# R2D2_Main_Board.net
KiCad netlist of a schematic drawn in EAGLE
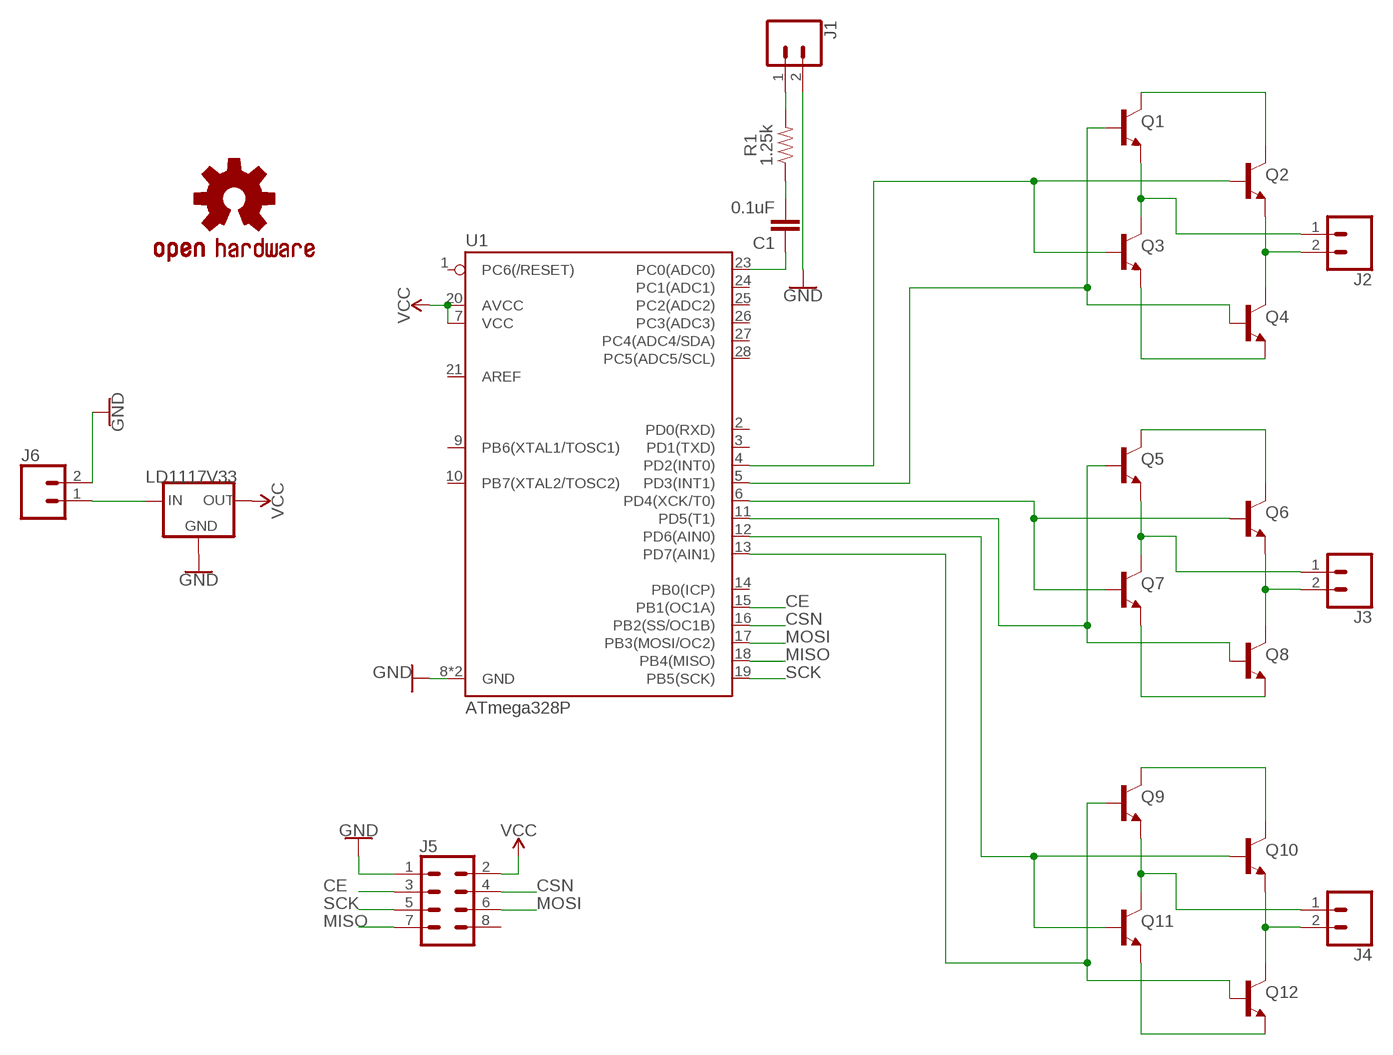
[diagram p0: schematic, sheet 1]

(export (version "E")
  (design (tool "Eeschema 10.0.6"))
  (components
    (comp (ref "C1")
      (value "0.1uF")
      (footprint "eagle-import:CAP-PTH-SMALL-KIT")
      (libsource (lib "eagle-import") (part "0.1UF-KIT-EZ-50V-20%"))
    )
    (comp (ref "J1")
      (value "CONN_02")
      (footprint "eagle-import:1X02")
      (libsource (lib "eagle-import") (part "CONN_02"))
    )
    (comp (ref "J2")
      (value "CONN_02")
      (footprint "eagle-import:1X02")
      (libsource (lib "eagle-import") (part "CONN_02"))
    )
    (comp (ref "J3")
      (value "CONN_02")
      (footprint "eagle-import:1X02")
      (libsource (lib "eagle-import") (part "CONN_02"))
    )
    (comp (ref "J4")
      (value "CONN_02")
      (footprint "eagle-import:1X02")
      (libsource (lib "eagle-import") (part "CONN_02"))
    )
    (comp (ref "J5")
      (value "CONN_04X2")
      (footprint "eagle-import:2X4")
      (libsource (lib "eagle-import") (part "CONN_04X2"))
    )
    (comp (ref "J6")
      (value "CONN_02")
      (footprint "eagle-import:1X02")
      (libsource (lib "eagle-import") (part "CONN_02"))
    )
    (comp (ref "LOGO1")
      (value "OSHW-LOGOL")
      (footprint "eagle-import:OSHW-LOGO-L")
      (libsource (lib "eagle-import") (part "OSHW-LOGOL"))
    )
    (comp (ref "Q1")
      (value "200mA/40V")
      (footprint "eagle-import:TO-92")
      (libsource (lib "eagle-import") (part "TRANS_NPN-2N3904"))
    )
    (comp (ref "Q2")
      (value "200mA/40V")
      (footprint "eagle-import:TO-92")
      (libsource (lib "eagle-import") (part "TRANS_NPN-2N3904"))
    )
    (comp (ref "Q3")
      (value "200mA/40V")
      (footprint "eagle-import:TO-92")
      (libsource (lib "eagle-import") (part "TRANS_NPN-2N3904"))
    )
    (comp (ref "Q4")
      (value "200mA/40V")
      (footprint "eagle-import:TO-92")
      (libsource (lib "eagle-import") (part "TRANS_NPN-2N3904"))
    )
    (comp (ref "Q5")
      (value "200mA/40V")
      (footprint "eagle-import:TO-92")
      (libsource (lib "eagle-import") (part "TRANS_NPN-2N3904"))
    )
    (comp (ref "Q6")
      (value "200mA/40V")
      (footprint "eagle-import:TO-92")
      (libsource (lib "eagle-import") (part "TRANS_NPN-2N3904"))
    )
    (comp (ref "Q7")
      (value "200mA/40V")
      (footprint "eagle-import:TO-92")
      (libsource (lib "eagle-import") (part "TRANS_NPN-2N3904"))
    )
    (comp (ref "Q8")
      (value "200mA/40V")
      (footprint "eagle-import:TO-92")
      (libsource (lib "eagle-import") (part "TRANS_NPN-2N3904"))
    )
    (comp (ref "Q9")
      (value "200mA/40V")
      (footprint "eagle-import:TO-92")
      (libsource (lib "eagle-import") (part "TRANS_NPN-2N3904"))
    )
    (comp (ref "Q10")
      (value "200mA/40V")
      (footprint "eagle-import:TO-92")
      (libsource (lib "eagle-import") (part "TRANS_NPN-2N3904"))
    )
    (comp (ref "Q11")
      (value "200mA/40V")
      (footprint "eagle-import:TO-92")
      (libsource (lib "eagle-import") (part "TRANS_NPN-2N3904"))
    )
    (comp (ref "Q12")
      (value "200mA/40V")
      (footprint "eagle-import:TO-92")
      (libsource (lib "eagle-import") (part "TRANS_NPN-2N3904"))
    )
    (comp (ref "R1")
      (value "1.25k")
      (footprint "eagle-import:AXIAL-0.3")
      (libsource (lib "eagle-import") (part "15KOHM-HORIZ-1/4W-5%"))
    )
    (comp (ref "U$1")
      (value "LD1117V33")
      (footprint "eagle-import:78XXL")
      (libsource (lib "eagle-import") (part "V_REG_LD1117VXX"))
    )
    (comp (ref "U1")
      (value "ATmega328P")
      (footprint "eagle-import:DIP28")
      (libsource (lib "eagle-import") (part "ATMEGA328P_PDIP"))
    )
  )
  (nets
    (net (code "1") (name "/CE") (class "Default")
      (node (ref "J5") (pin "3") (pinfunction "3_3") (pintype "passive"))
      (node (ref "U1") (pin "15") (pinfunction "PB1(OC1A)_15") (pintype "bidirectional"))
    )
    (net (code "2") (name "/CSN") (class "Default")
      (node (ref "J5") (pin "4") (pinfunction "4_4") (pintype "passive"))
      (node (ref "U1") (pin "16") (pinfunction "PB2(SS/OC1B)_16") (pintype "bidirectional"))
    )
    (net (code "3") (name "/MISO") (class "Default")
      (node (ref "J5") (pin "7") (pinfunction "7_7") (pintype "passive"))
      (node (ref "U1") (pin "18") (pinfunction "PB4(MISO)_18") (pintype "bidirectional"))
    )
    (net (code "4") (name "/MOSI") (class "Default")
      (node (ref "J5") (pin "6") (pinfunction "6_6") (pintype "passive"))
      (node (ref "U1") (pin "17") (pinfunction "PB3(MOSI/OC2)_17") (pintype "bidirectional"))
    )
    (net (code "5") (name "/SCK") (class "Default")
      (node (ref "J5") (pin "5") (pinfunction "5_5") (pintype "passive"))
      (node (ref "U1") (pin "19") (pinfunction "PB5(SCK)_19") (pintype "bidirectional"))
    )
    (net (code "6") (name "GND") (class "Default")
      (node (ref "J1") (pin "2") (pinfunction "2_2") (pintype "passive"))
      (node (ref "J5") (pin "1") (pinfunction "1_1") (pintype "passive"))
      (node (ref "J6") (pin "2") (pinfunction "2_2") (pintype "passive"))
      (node (ref "U$1") (pin "IN") (pinfunction "GND_IN") (pintype "input"))
      (node (ref "U1") (pin "22") (pinfunction "GND_22") (pintype "bidirectional"))
      (node (ref "U1") (pin "8") (pinfunction "GND_8") (pintype "bidirectional"))
    )
    (net (code "7") (name "Net-(Q1-B)") (class "Default")
      (node (ref "Q1") (pin "2") (pinfunction "B_2") (pintype "passive"))
      (node (ref "Q4") (pin "2") (pinfunction "B_2") (pintype "passive"))
      (node (ref "U1") (pin "5") (pinfunction "PD3(INT1)_5") (pintype "bidirectional"))
    )
    (net (code "8") (name "Net-(Q1-C)") (class "Default")
      (node (ref "Q1") (pin "3") (pinfunction "C_3") (pintype "passive"))
      (node (ref "Q2") (pin "3") (pinfunction "C_3") (pintype "passive"))
    )
    (net (code "9") (name "Net-(Q1-E)") (class "Default")
      (node (ref "J2") (pin "1") (pinfunction "1_1") (pintype "passive"))
      (node (ref "Q1") (pin "1") (pinfunction "E_1") (pintype "passive"))
      (node (ref "Q3") (pin "3") (pinfunction "C_3") (pintype "passive"))
    )
    (net (code "10") (name "Net-(Q2-B)") (class "Default")
      (node (ref "Q2") (pin "2") (pinfunction "B_2") (pintype "passive"))
      (node (ref "Q3") (pin "2") (pinfunction "B_2") (pintype "passive"))
      (node (ref "U1") (pin "4") (pinfunction "PD2(INT0)_4") (pintype "bidirectional"))
    )
    (net (code "11") (name "Net-(Q2-E)") (class "Default")
      (node (ref "J2") (pin "2") (pinfunction "2_2") (pintype "passive"))
      (node (ref "Q2") (pin "1") (pinfunction "E_1") (pintype "passive"))
      (node (ref "Q4") (pin "3") (pinfunction "C_3") (pintype "passive"))
    )
    (net (code "12") (name "Net-(Q3-E)") (class "Default")
      (node (ref "Q3") (pin "1") (pinfunction "E_1") (pintype "passive"))
      (node (ref "Q4") (pin "1") (pinfunction "E_1") (pintype "passive"))
    )
    (net (code "13") (name "Net-(Q5-B)") (class "Default")
      (node (ref "Q5") (pin "2") (pinfunction "B_2") (pintype "passive"))
      (node (ref "Q8") (pin "2") (pinfunction "B_2") (pintype "passive"))
      (node (ref "U1") (pin "11") (pinfunction "PD5(T1)_11") (pintype "bidirectional"))
    )
    (net (code "14") (name "Net-(Q5-C)") (class "Default")
      (node (ref "Q5") (pin "3") (pinfunction "C_3") (pintype "passive"))
      (node (ref "Q6") (pin "3") (pinfunction "C_3") (pintype "passive"))
    )
    (net (code "15") (name "Net-(Q5-E)") (class "Default")
      (node (ref "J3") (pin "1") (pinfunction "1_1") (pintype "passive"))
      (node (ref "Q5") (pin "1") (pinfunction "E_1") (pintype "passive"))
      (node (ref "Q7") (pin "3") (pinfunction "C_3") (pintype "passive"))
    )
    (net (code "16") (name "Net-(Q6-B)") (class "Default")
      (node (ref "Q6") (pin "2") (pinfunction "B_2") (pintype "passive"))
      (node (ref "Q7") (pin "2") (pinfunction "B_2") (pintype "passive"))
      (node (ref "U1") (pin "6") (pinfunction "PD4(XCK/T0)_6") (pintype "bidirectional"))
    )
    (net (code "17") (name "Net-(Q6-E)") (class "Default")
      (node (ref "J3") (pin "2") (pinfunction "2_2") (pintype "passive"))
      (node (ref "Q6") (pin "1") (pinfunction "E_1") (pintype "passive"))
      (node (ref "Q8") (pin "3") (pinfunction "C_3") (pintype "passive"))
    )
    (net (code "18") (name "Net-(Q7-E)") (class "Default")
      (node (ref "Q7") (pin "1") (pinfunction "E_1") (pintype "passive"))
      (node (ref "Q8") (pin "1") (pinfunction "E_1") (pintype "passive"))
    )
    (net (code "19") (name "Net-(Q10-B)") (class "Default")
      (node (ref "Q10") (pin "2") (pinfunction "B_2") (pintype "passive"))
      (node (ref "Q11") (pin "2") (pinfunction "B_2") (pintype "passive"))
      (node (ref "U1") (pin "12") (pinfunction "PD6(AIN0)_12") (pintype "bidirectional"))
    )
    (net (code "20") (name "Net-(Q10-C)") (class "Default")
      (node (ref "Q10") (pin "3") (pinfunction "C_3") (pintype "passive"))
      (node (ref "Q9") (pin "3") (pinfunction "C_3") (pintype "passive"))
    )
    (net (code "21") (name "Net-(Q10-E)") (class "Default")
      (node (ref "J4") (pin "2") (pinfunction "2_2") (pintype "passive"))
      (node (ref "Q10") (pin "1") (pinfunction "E_1") (pintype "passive"))
      (node (ref "Q12") (pin "3") (pinfunction "C_3") (pintype "passive"))
    )
    (net (code "22") (name "Net-(Q11-C)") (class "Default")
      (node (ref "J4") (pin "1") (pinfunction "1_1") (pintype "passive"))
      (node (ref "Q11") (pin "3") (pinfunction "C_3") (pintype "passive"))
      (node (ref "Q9") (pin "1") (pinfunction "E_1") (pintype "passive"))
    )
    (net (code "23") (name "Net-(Q11-E)") (class "Default")
      (node (ref "Q11") (pin "1") (pinfunction "E_1") (pintype "passive"))
      (node (ref "Q12") (pin "1") (pinfunction "E_1") (pintype "passive"))
    )
    (net (code "24") (name "Net-(Q12-B)") (class "Default")
      (node (ref "Q12") (pin "2") (pinfunction "B_2") (pintype "passive"))
      (node (ref "Q9") (pin "2") (pinfunction "B_2") (pintype "passive"))
      (node (ref "U1") (pin "13") (pinfunction "PD7(AIN1)_13") (pintype "bidirectional"))
    )
    (net (code "25") (name "Net-(R1-1)") (class "Default")
      (node (ref "C1") (pin "2") (pinfunction "2_2") (pintype "passive"))
      (node (ref "R1") (pin "P$1") (pinfunction "1_P$1") (pintype "passive"))
    )
    (net (code "26") (name "Net-(R1-2)") (class "Default")
      (node (ref "J1") (pin "1") (pinfunction "1_1") (pintype "passive"))
      (node (ref "R1") (pin "P$2") (pinfunction "2_P$2") (pintype "passive"))
    )
    (net (code "27") (name "Net-(U$1-IN)") (class "Default")
      (node (ref "J6") (pin "1") (pinfunction "1_1") (pintype "passive"))
      (node (ref "U$1") (pin "OUT") (pinfunction "IN_OUT") (pintype "input"))
    )
    (net (code "28") (name "Net-(U1-PC0(ADC0))") (class "Default")
      (node (ref "C1") (pin "1") (pinfunction "1_1") (pintype "passive"))
      (node (ref "U1") (pin "23") (pinfunction "PC0(ADC0)_23") (pintype "bidirectional"))
    )
    (net (code "29") (name "VCC") (class "Default")
      (node (ref "J5") (pin "2") (pinfunction "2_2") (pintype "passive"))
      (node (ref "U$1") (pin "GND") (pinfunction "OUT_GND") (pintype "passive"))
      (node (ref "U1") (pin "20") (pinfunction "AVCC_20") (pintype "bidirectional"))
      (node (ref "U1") (pin "7") (pinfunction "VCC_7") (pintype "bidirectional"))
    )
    (net (code "30") (name "unconnected-(J5-Pad8)") (class "Default")
      (node (ref "J5") (pin "8") (pinfunction "8_8") (pintype "passive"))
    )
    (net (code "31") (name "unconnected-(U1-AREF-Pad21)") (class "Default")
      (node (ref "U1") (pin "21") (pinfunction "AREF_21") (pintype "bidirectional"))
    )
    (net (code "32") (name "unconnected-(U1-PB0(ICP)-Pad14)") (class "Default")
      (node (ref "U1") (pin "14") (pinfunction "PB0(ICP)_14") (pintype "bidirectional"))
    )
    (net (code "33") (name "unconnected-(U1-PB6(XTAL1{slash}TOSC1)-Pad9)") (class "Default")
      (node (ref "U1") (pin "9") (pinfunction "PB6(XTAL1/TOSC1)_9") (pintype "bidirectional"))
    )
    (net (code "34") (name "unconnected-(U1-PB7(XTAL2{slash}TOSC2)-Pad10)") (class "Default")
      (node (ref "U1") (pin "10") (pinfunction "PB7(XTAL2/TOSC2)_10") (pintype "bidirectional"))
    )
    (net (code "35") (name "unconnected-(U1-PC1(ADC1)-Pad24)") (class "Default")
      (node (ref "U1") (pin "24") (pinfunction "PC1(ADC1)_24") (pintype "bidirectional"))
    )
    (net (code "36") (name "unconnected-(U1-PC2(ADC2)-Pad25)") (class "Default")
      (node (ref "U1") (pin "25") (pinfunction "PC2(ADC2)_25") (pintype "bidirectional"))
    )
    (net (code "37") (name "unconnected-(U1-PC3(ADC3)-Pad26)") (class "Default")
      (node (ref "U1") (pin "26") (pinfunction "PC3(ADC3)_26") (pintype "bidirectional"))
    )
    (net (code "38") (name "unconnected-(U1-PC4(ADC4{slash}SDA)-Pad27)") (class "Default")
      (node (ref "U1") (pin "27") (pinfunction "PC4(ADC4/SDA)_27") (pintype "bidirectional"))
    )
    (net (code "39") (name "unconnected-(U1-PC5(ADC5{slash}SCL)-Pad28)") (class "Default")
      (node (ref "U1") (pin "28") (pinfunction "PC5(ADC5/SCL)_28") (pintype "bidirectional"))
    )
    (net (code "40") (name "unconnected-(U1-PC6({slash}RESET)-Pad1)") (class "Default")
      (node (ref "U1") (pin "1") (pinfunction "PC6(/RESET)_1") (pintype "bidirectional"))
    )
    (net (code "41") (name "unconnected-(U1-PD0(RXD)-Pad2)") (class "Default")
      (node (ref "U1") (pin "2") (pinfunction "PD0(RXD)_2") (pintype "bidirectional"))
    )
    (net (code "42") (name "unconnected-(U1-PD1(TXD)-Pad3)") (class "Default")
      (node (ref "U1") (pin "3") (pinfunction "PD1(TXD)_3") (pintype "bidirectional"))
    )
  )
)
